# 4_-_POWER.net
KiCad netlist of a schematic drawn in Altium Designer
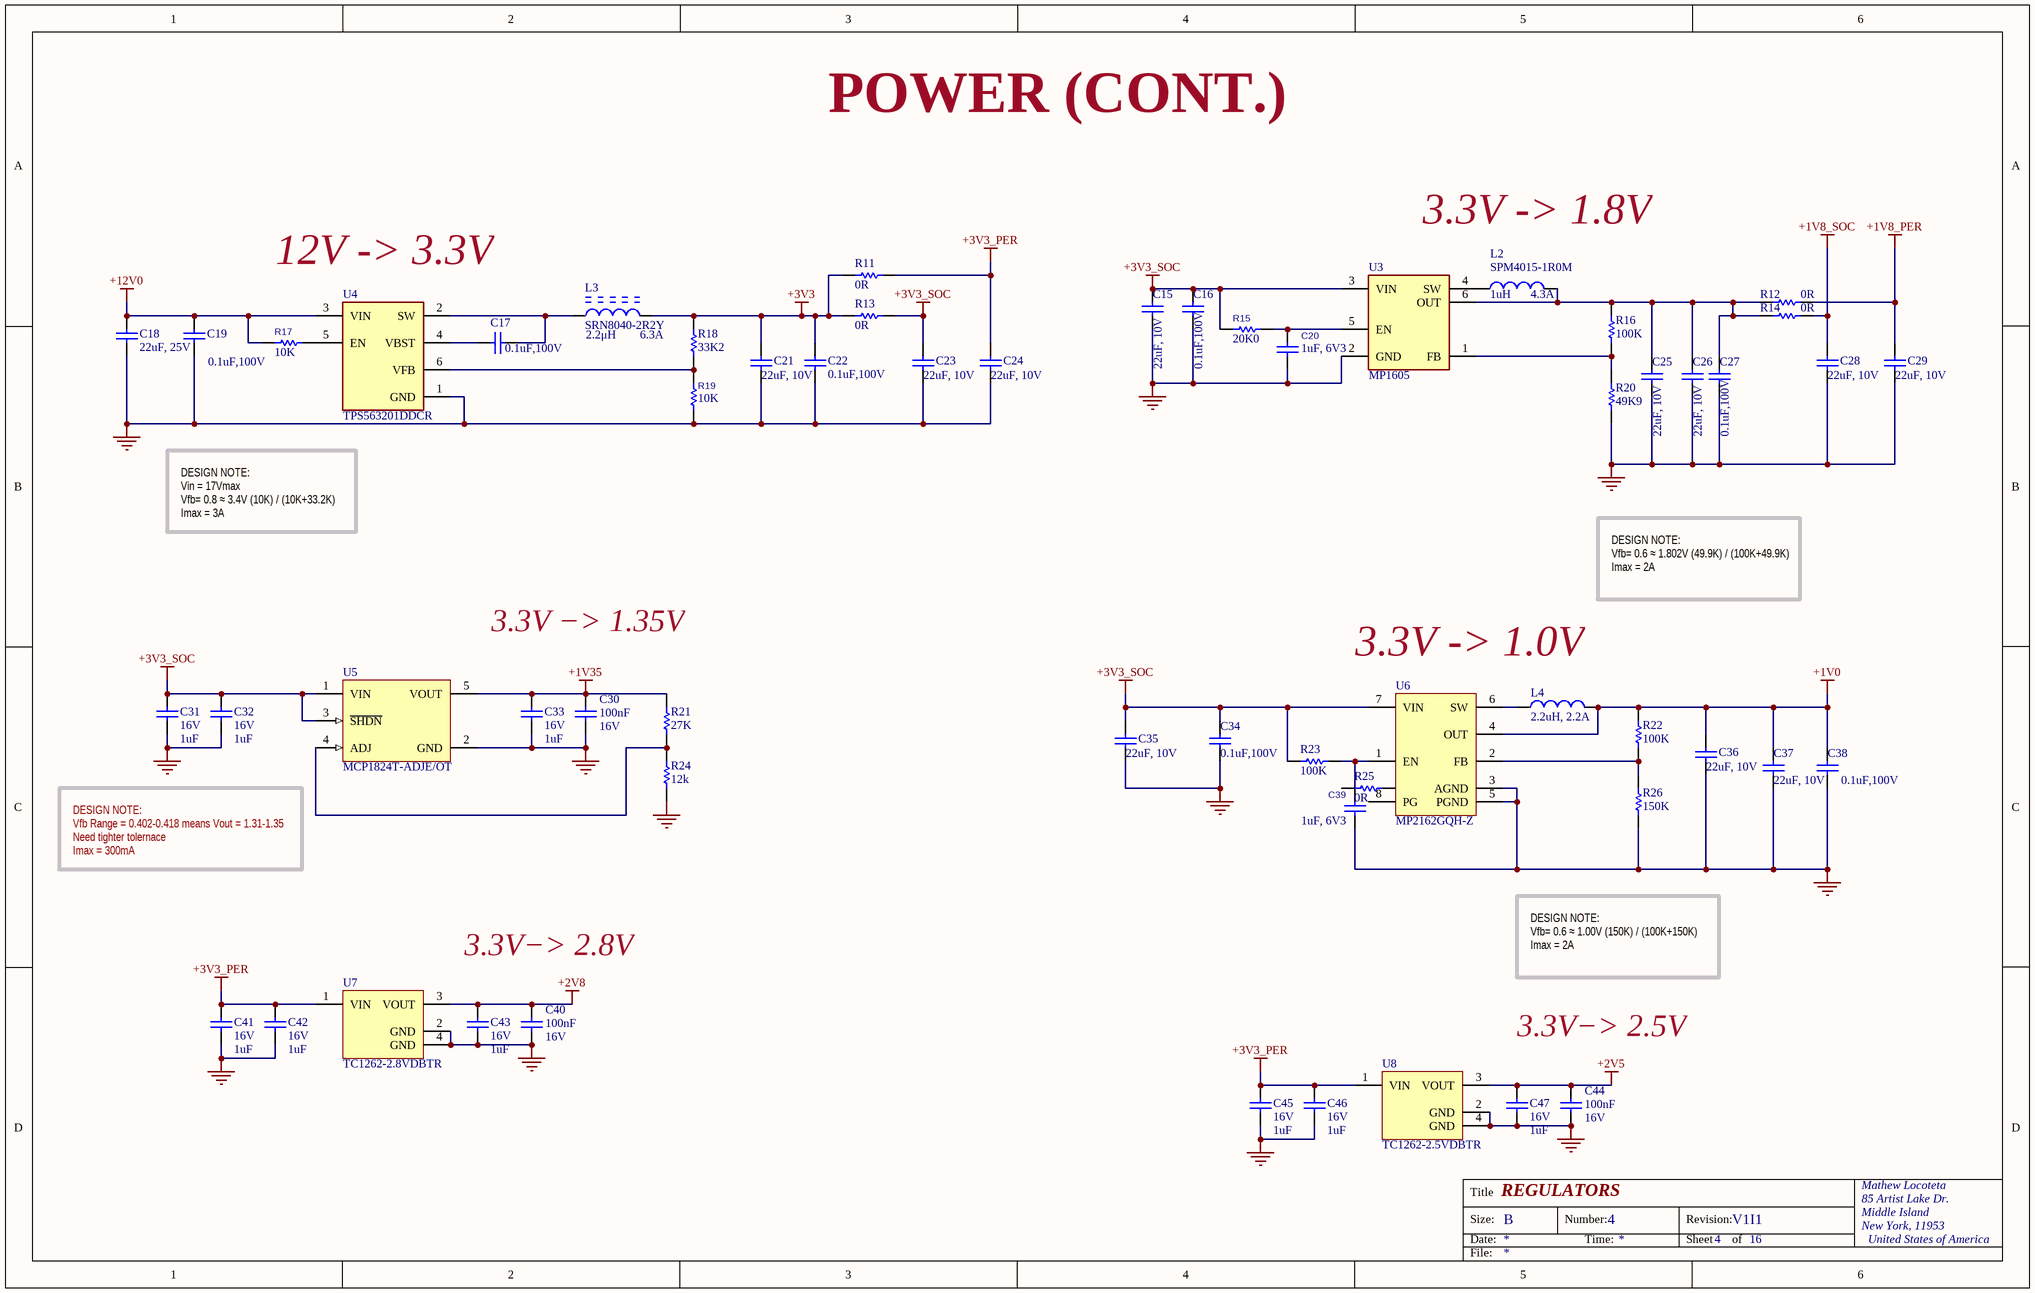
[diagram p0: [4] - POWER (CONT).SchDoc]

(export (version "E")
  (design (tool "Eeschema 10.0.6"))
  (components
    (comp (ref "C15")
      (value "22uF, 10V")
      (footprint "C0805")
      (description "MURATA - GRM21BR61A226ME51L - CAP, MLCC, X5R, 22UF, 10V, 0805")
      (fields
        (field (name "MANUFACTURER") "Murata")
        (field (name "MANUFACTURER PART NUMBER") "GRM21BR61A226ME51L")
      )
      (libsource (lib "DVXC4+ ECU (2)") (part "GRM21BR61A226ME51L"))
    )
    (comp (ref "C16")
      (value "0.1uF,100V")
      (footprint "C0805")
      (description "CAP CER 0.1UF 100V X7R 0805")
      (fields
        (field (name "MANUFACTURER") "Samsung")
        (field (name "MANUFACTURER PART NUMBER") "CL21B104KCFWPNE")
      )
      (libsource (lib "DVXC5 ECU") (part "CL21B104KCFWPNE"))
    )
    (comp (ref "C17")
      (value "0.1uF,100V")
      (footprint "C0805")
      (description "CAP CER 0.1UF 100V X7R 0805")
      (fields
        (field (name "MANUFACTURER") "Samsung")
        (field (name "MANUFACTURER PART NUMBER") "CL21B104KCFWPNE")
      )
      (libsource (lib "DVXC5 ECU") (part "CL21B104KCFWPNE"))
    )
    (comp (ref "C18")
      (value "22uF, 25V")
      (footprint "C1210")
      (description "22µF ±20% 25V Ceramic Capacitor X7R 1210 (3225 Metric)")
      (fields
        (field (name "MANUFACTURER") "Taiyo Yuden")
        (field (name "MANUFACTURER PART NUMBER") "TMK325B7226MMHP")
      )
      (libsource (lib "DVXC4+ ECU (2)") (part "TMK325B7226MMHP"))
    )
    (comp (ref "C19")
      (value "0.1uF,100V")
      (footprint "C0805")
      (description "CAP CER 0.1UF 100V X7R 0805")
      (fields
        (field (name "MANUFACTURER") "Samsung")
        (field (name "MANUFACTURER PART NUMBER") "CL21B104KCFWPNE")
      )
      (libsource (lib "DVXC5 ECU") (part "CL21B104KCFWPNE"))
    )
    (comp (ref "C20")
      (value "1uF, 6V3")
      (footprint "C0402")
      (description "MURATA - GRT155R70J105KE01D - CAP, 1µF, 6.3V, 10%, X7R, 0402")
      (fields
        (field (name "MANUFACTURER") "Murata")
        (field (name "MANUFACTURER PART NUMBER") "GRT155R70J105KE01D")
      )
      (libsource (lib "DVXC4+ ECU (2)") (part "GRT155R70J105KE01D"))
    )
    (comp (ref "C21")
      (value "22uF, 10V")
      (footprint "C0805")
      (description "MURATA - GRM21BR61A226ME51L - CAP, MLCC, X5R, 22UF, 10V, 0805")
      (fields
        (field (name "MANUFACTURER") "Murata")
        (field (name "MANUFACTURER PART NUMBER") "GRM21BR61A226ME51L")
      )
      (libsource (lib "DVXC4+ ECU (2)") (part "GRM21BR61A226ME51L"))
    )
    (comp (ref "C22")
      (value "0.1uF,100V")
      (footprint "C0805")
      (description "CAP CER 0.1UF 100V X7R 0805")
      (fields
        (field (name "MANUFACTURER") "Samsung")
        (field (name "MANUFACTURER PART NUMBER") "CL21B104KCFWPNE")
      )
      (libsource (lib "DVXC5 ECU") (part "CL21B104KCFWPNE"))
    )
    (comp (ref "C23")
      (value "22uF, 10V")
      (footprint "C0805")
      (description "MURATA - GRM21BR61A226ME51L - CAP, MLCC, X5R, 22UF, 10V, 0805")
      (fields
        (field (name "MANUFACTURER") "Murata")
        (field (name "MANUFACTURER PART NUMBER") "GRM21BR61A226ME51L")
      )
      (libsource (lib "DVXC4+ ECU (2)") (part "GRM21BR61A226ME51L"))
    )
    (comp (ref "C24")
      (value "22uF, 10V")
      (footprint "C0805")
      (description "MURATA - GRM21BR61A226ME51L - CAP, MLCC, X5R, 22UF, 10V, 0805")
      (fields
        (field (name "MANUFACTURER") "Murata")
        (field (name "MANUFACTURER PART NUMBER") "GRM21BR61A226ME51L")
      )
      (libsource (lib "DVXC4+ ECU (2)") (part "GRM21BR61A226ME51L"))
    )
    (comp (ref "C25")
      (value "22uF, 10V")
      (footprint "C0805")
      (description "MURATA - GRM21BR61A226ME51L - CAP, MLCC, X5R, 22UF, 10V, 0805")
      (fields
        (field (name "MANUFACTURER") "Murata")
        (field (name "MANUFACTURER PART NUMBER") "GRM21BR61A226ME51L")
      )
      (libsource (lib "DVXC4+ ECU (2)") (part "GRM21BR61A226ME51L"))
    )
    (comp (ref "C26")
      (value "22uF, 10V")
      (footprint "C0805")
      (description "MURATA - GRM21BR61A226ME51L - CAP, MLCC, X5R, 22UF, 10V, 0805")
      (fields
        (field (name "MANUFACTURER") "Murata")
        (field (name "MANUFACTURER PART NUMBER") "GRM21BR61A226ME51L")
      )
      (libsource (lib "DVXC4+ ECU (2)") (part "GRM21BR61A226ME51L"))
    )
    (comp (ref "C27")
      (value "0.1uF,100V")
      (footprint "C0805")
      (description "CAP CER 0.1UF 100V X7R 0805")
      (fields
        (field (name "MANUFACTURER") "Samsung")
        (field (name "MANUFACTURER PART NUMBER") "CL21B104KCFWPNE")
      )
      (libsource (lib "DVXC5 ECU") (part "CL21B104KCFWPNE"))
    )
    (comp (ref "C28")
      (value "22uF, 10V")
      (footprint "C0805")
      (description "MURATA - GRM21BR61A226ME51L - CAP, MLCC, X5R, 22UF, 10V, 0805")
      (fields
        (field (name "MANUFACTURER") "Murata")
        (field (name "MANUFACTURER PART NUMBER") "GRM21BR61A226ME51L")
      )
      (libsource (lib "DVXC4+ ECU (2)") (part "GRM21BR61A226ME51L"))
    )
    (comp (ref "C29")
      (value "22uF, 10V")
      (footprint "C0805")
      (description "MURATA - GRM21BR61A226ME51L - CAP, MLCC, X5R, 22UF, 10V, 0805")
      (fields
        (field (name "MANUFACTURER") "Murata")
        (field (name "MANUFACTURER PART NUMBER") "GRM21BR61A226ME51L")
      )
      (libsource (lib "DVXC4+ ECU (2)") (part "GRM21BR61A226ME51L"))
    )
    (comp (ref "C30")
      (value "0.1uF,16V")
      (footprint "C0402")
      (description "CAP CER 0.1UF 16V X7R 0402")
      (fields
        (field (name "MANUFACTURER") "Samsung")
        (field (name "MANUFACTURER PART NUMBER") "CL05B104KO5VPNC")
        (field (name "CAPACITANCE") "100nF")
        (field (name "VOLTAGE RATING") "16V")
      )
      (libsource (lib "DVXC4+ ECU (2)") (part "CL05B104KO5VPNC"))
    )
    (comp (ref "C31")
      (value "1uF")
      (footprint "C0603")
      (description "Multilayer Ceramic Capacitors MLCC - SMD/SMT 1uF 16V X7R +/-10% 0603 AEC-Q200")
      (fields
        (field (name "MANUFACTURER") "Taiyo Yuden")
        (field (name "MANUFACTURER PART NUMBER") "EMK107B7105KAHT")
        (field (name "VOLTAGE RATING") "16V")
        (field (name "CAPACITANCE") "1uF")
      )
      (libsource (lib "DVXC4+ ECU (2)") (part "EMK107B7105KAHT"))
    )
    (comp (ref "C32")
      (value "1uF")
      (footprint "C0603")
      (description "Multilayer Ceramic Capacitors MLCC - SMD/SMT 1uF 16V X7R +/-10% 0603 AEC-Q200")
      (fields
        (field (name "MANUFACTURER") "Taiyo Yuden")
        (field (name "MANUFACTURER PART NUMBER") "EMK107B7105KAHT")
        (field (name "VOLTAGE RATING") "16V")
        (field (name "CAPACITANCE") "1uF")
      )
      (libsource (lib "DVXC4+ ECU (2)") (part "EMK107B7105KAHT"))
    )
    (comp (ref "C33")
      (value "1uF")
      (footprint "C0603")
      (description "Multilayer Ceramic Capacitors MLCC - SMD/SMT 1uF 16V X7R +/-10% 0603 AEC-Q200")
      (fields
        (field (name "MANUFACTURER") "Taiyo Yuden")
        (field (name "MANUFACTURER PART NUMBER") "EMK107B7105KAHT")
        (field (name "VOLTAGE RATING") "16V")
        (field (name "CAPACITANCE") "1uF")
      )
      (libsource (lib "DVXC4+ ECU (2)") (part "EMK107B7105KAHT"))
    )
    (comp (ref "C34")
      (value "0.1uF,100V")
      (footprint "C0805")
      (description "CAP CER 0.1UF 100V X7R 0805")
      (fields
        (field (name "MANUFACTURER") "Samsung")
        (field (name "MANUFACTURER PART NUMBER") "CL21B104KCFWPNE")
      )
      (libsource (lib "DVXC5 ECU") (part "CL21B104KCFWPNE"))
    )
    (comp (ref "C35")
      (value "22uF, 10V")
      (footprint "C0805")
      (description "MURATA - GRM21BR61A226ME51L - CAP, MLCC, X5R, 22UF, 10V, 0805")
      (fields
        (field (name "MANUFACTURER") "Murata")
        (field (name "MANUFACTURER PART NUMBER") "GRM21BR61A226ME51L")
      )
      (libsource (lib "DVXC4+ ECU (2)") (part "GRM21BR61A226ME51L"))
    )
    (comp (ref "C36")
      (value "22uF, 10V")
      (footprint "C0805")
      (description "MURATA - GRM21BR61A226ME51L - CAP, MLCC, X5R, 22UF, 10V, 0805")
      (fields
        (field (name "MANUFACTURER") "Murata")
        (field (name "MANUFACTURER PART NUMBER") "GRM21BR61A226ME51L")
      )
      (libsource (lib "DVXC4+ ECU (2)") (part "GRM21BR61A226ME51L"))
    )
    (comp (ref "C37")
      (value "22uF, 10V")
      (footprint "C0805")
      (description "MURATA - GRM21BR61A226ME51L - CAP, MLCC, X5R, 22UF, 10V, 0805")
      (fields
        (field (name "MANUFACTURER") "Murata")
        (field (name "MANUFACTURER PART NUMBER") "GRM21BR61A226ME51L")
      )
      (libsource (lib "DVXC4+ ECU (2)") (part "GRM21BR61A226ME51L"))
    )
    (comp (ref "C38")
      (value "0.1uF,100V")
      (footprint "C0805")
      (description "CAP CER 0.1UF 100V X7R 0805")
      (fields
        (field (name "MANUFACTURER") "Samsung")
        (field (name "MANUFACTURER PART NUMBER") "CL21B104KCFWPNE")
      )
      (libsource (lib "DVXC5 ECU") (part "CL21B104KCFWPNE"))
    )
    (comp (ref "C39")
      (value "1uF, 6V3")
      (footprint "C0402")
      (description "MURATA - GRT155R70J105KE01D - CAP, 1µF, 6.3V, 10%, X7R, 0402")
      (fields
        (field (name "MANUFACTURER") "Murata")
        (field (name "MANUFACTURER PART NUMBER") "GRT155R70J105KE01D")
      )
      (libsource (lib "DVXC5 ECU") (part "GRT155R70J105KE01D"))
    )
    (comp (ref "C40")
      (value "0.1uF,16V")
      (footprint "C0402")
      (description "CAP CER 0.1UF 16V X7R 0402")
      (fields
        (field (name "MANUFACTURER") "Samsung")
        (field (name "MANUFACTURER PART NUMBER") "CL05B104KO5VPNC")
        (field (name "CAPACITANCE") "100nF")
        (field (name "VOLTAGE RATING") "16V")
      )
      (libsource (lib "DVXC4+ ECU (2)") (part "CL05B104KO5VPNC"))
    )
    (comp (ref "C41")
      (value "1uF")
      (footprint "C0603")
      (description "Multilayer Ceramic Capacitors MLCC - SMD/SMT 1uF 16V X7R +/-10% 0603 AEC-Q200")
      (fields
        (field (name "MANUFACTURER") "Taiyo Yuden")
        (field (name "MANUFACTURER PART NUMBER") "EMK107B7105KAHT")
        (field (name "VOLTAGE RATING") "16V")
        (field (name "CAPACITANCE") "1uF")
      )
      (libsource (lib "DVXC4+ ECU (2)") (part "EMK107B7105KAHT"))
    )
    (comp (ref "C42")
      (value "1uF")
      (footprint "C0603")
      (description "Multilayer Ceramic Capacitors MLCC - SMD/SMT 1uF 16V X7R +/-10% 0603 AEC-Q200")
      (fields
        (field (name "MANUFACTURER") "Taiyo Yuden")
        (field (name "MANUFACTURER PART NUMBER") "EMK107B7105KAHT")
        (field (name "VOLTAGE RATING") "16V")
        (field (name "CAPACITANCE") "1uF")
      )
      (libsource (lib "DVXC4+ ECU (2)") (part "EMK107B7105KAHT"))
    )
    (comp (ref "C43")
      (value "1uF")
      (footprint "C0603")
      (description "Multilayer Ceramic Capacitors MLCC - SMD/SMT 1uF 16V X7R +/-10% 0603 AEC-Q200")
      (fields
        (field (name "MANUFACTURER") "Taiyo Yuden")
        (field (name "MANUFACTURER PART NUMBER") "EMK107B7105KAHT")
        (field (name "VOLTAGE RATING") "16V")
        (field (name "CAPACITANCE") "1uF")
      )
      (libsource (lib "DVXC4+ ECU (2)") (part "EMK107B7105KAHT"))
    )
    (comp (ref "C44")
      (value "0.1uF,16V")
      (footprint "C0402")
      (description "CAP CER 0.1UF 16V X7R 0402")
      (fields
        (field (name "MANUFACTURER") "Samsung")
        (field (name "MANUFACTURER PART NUMBER") "CL05B104KO5VPNC")
        (field (name "CAPACITANCE") "100nF")
        (field (name "VOLTAGE RATING") "16V")
      )
      (libsource (lib "DVXC4+ ECU (2)") (part "CL05B104KO5VPNC"))
    )
    (comp (ref "C45")
      (value "1uF")
      (footprint "C0603")
      (description "Multilayer Ceramic Capacitors MLCC - SMD/SMT 1uF 16V X7R +/-10% 0603 AEC-Q200")
      (fields
        (field (name "MANUFACTURER") "Taiyo Yuden")
        (field (name "MANUFACTURER PART NUMBER") "EMK107B7105KAHT")
        (field (name "VOLTAGE RATING") "16V")
        (field (name "CAPACITANCE") "1uF")
      )
      (libsource (lib "DVXC4+ ECU (2)") (part "EMK107B7105KAHT"))
    )
    (comp (ref "C46")
      (value "1uF")
      (footprint "C0603")
      (description "Multilayer Ceramic Capacitors MLCC - SMD/SMT 1uF 16V X7R +/-10% 0603 AEC-Q200")
      (fields
        (field (name "MANUFACTURER") "Taiyo Yuden")
        (field (name "MANUFACTURER PART NUMBER") "EMK107B7105KAHT")
        (field (name "VOLTAGE RATING") "16V")
        (field (name "CAPACITANCE") "1uF")
      )
      (libsource (lib "DVXC4+ ECU (2)") (part "EMK107B7105KAHT"))
    )
    (comp (ref "C47")
      (value "1uF")
      (footprint "C0603")
      (description "Multilayer Ceramic Capacitors MLCC - SMD/SMT 1uF 16V X7R +/-10% 0603 AEC-Q200")
      (fields
        (field (name "MANUFACTURER") "Taiyo Yuden")
        (field (name "MANUFACTURER PART NUMBER") "EMK107B7105KAHT")
        (field (name "VOLTAGE RATING") "16V")
        (field (name "CAPACITANCE") "1uF")
      )
      (libsource (lib "DVXC4+ ECU (2)") (part "EMK107B7105KAHT"))
    )
    (comp (ref "L2")
      (value "SPM4015-1R0M")
      (description "Fixed Inductors 1.0uH 39mOhms 6.7A 4.4x4.1x1.5mm")
      (fields
        (field (name "MANUFACTURER") "TDK")
        (field (name "TOLERANCE") "20%")
        (field (name "INDUCTANCE") "1uH")
        (field (name "CURRENT RATING") "4.3A")
      )
      (libsource (lib "DVXC4+ ECU (2)") (part "SPM4015-1R0M"))
    )
    (comp (ref "L3")
      (value "SRN8040-2R2Y")
      (footprint "BOUR-SRN8040_V")
      (fields
        (field (name "MANUFACTURER") "Bourns")
        (field (name "TOLERANCE") "±30%")
        (field (name "CURRENT, RATING") "6.3A")
        (field (name "INDUCTANCE") "2.2μH")
      )
      (libsource (lib "Altium Content Vault") (part "IND-FERR-2"))
    )
    (comp (ref "L4")
      (value "2.2uH, 2.2A")
      (description "FIXED IND 2.2UH 2.2A 108 MOHM")
      (fields
        (field (name "MANUFACTURER") "Murata")
        (field (name "MANUFACTURER PART NUMBER") "1239AS-H-2R2M=P2")
      )
      (libsource (lib "DVXC4+ ECU (2)") (part "1239AS-H-2R2M=P2"))
    )
    (comp (ref "R11")
      (value "0R")
      (footprint "r0805")
      (fields
        (field (name "MANUFACTURER") "Stackpole Electronics")
        (field (name "MANUFACTURER PART NUMBER") "RMCF0805ZT0R00")
      )
      (libsource (lib "DVXC4+ ECU (2)") (part "RMCF0805ZT0R00"))
    )
    (comp (ref "R12")
      (value "0R")
      (footprint "r0805")
      (fields
        (field (name "MANUFACTURER") "Stackpole Electronics")
        (field (name "MANUFACTURER PART NUMBER") "RMCF0805ZT0R00")
      )
      (libsource (lib "DVXC4+ ECU (2)") (part "RMCF0805ZT0R00"))
    )
    (comp (ref "R13")
      (value "0R")
      (footprint "r0805")
      (fields
        (field (name "MANUFACTURER") "Stackpole Electronics")
        (field (name "MANUFACTURER PART NUMBER") "RMCF0805ZT0R00")
      )
      (libsource (lib "DVXC4+ ECU (2)") (part "RMCF0805ZT0R00"))
    )
    (comp (ref "R14")
      (value "0R")
      (footprint "r0805")
      (fields
        (field (name "MANUFACTURER") "Stackpole Electronics")
        (field (name "MANUFACTURER PART NUMBER") "RMCF0805ZT0R00")
      )
      (libsource (lib "DVXC4+ ECU (2)") (part "RMCF0805ZT0R00"))
    )
    (comp (ref "R15")
      (value "20K0")
      (footprint "R0402")
      (description "RES 20K OHM 1% 1/16W 0402")
      (fields (field (name "TOLERANCE") "1%"))
      (libsource (lib "DVXC4+ ECU (2)") (part "RMCF0402FT20K0"))
    )
    (comp (ref "R16")
      (value "100K")
      (footprint "R0402")
      (description "RES 100K OHM 1% 1/16W 0402")
      (fields
        (field (name "MANUFACTURER") "Stackpole Electronics")
        (field (name "MANUFACTURER PART NUMBER") "RMCF0402FT100K")
      )
      (libsource (lib "DVXC4+ ECU (2)") (part "RMCF0402FT100K"))
    )
    (comp (ref "R17")
      (value "10K")
      (footprint "R0402")
      (description "RES 10K OHM 1% 1/16W 0402")
      (fields
        (field (name "MANUFACTURER") "Stackpole Electronics")
        (field (name "MANUFACTURER PART NUMBER") "RMCF0402FT10K0")
      )
      (libsource (lib "DVXC4+ ECU (2)") (part "RMCF0402FT10K0"))
    )
    (comp (ref "R18")
      (value "33K2")
      (footprint "R0402")
      (description "RES 33.2K OHM 1% 1/16W 0402")
      (fields
        (field (name "MANUFACTURER") "Stackpole Electronics")
        (field (name "MANUFACTURER PART NUMBER") "RMCF0402FT33K2")
      )
      (libsource (lib "DVXC4+ ECU (2)") (part "RMCF0402FT33K2"))
    )
    (comp (ref "R19")
      (value "10K")
      (footprint "R0402")
      (description "RES 10K OHM 1% 1/16W 0402")
      (fields
        (field (name "MANUFACTURER") "Stackpole Electronics")
        (field (name "MANUFACTURER PART NUMBER") "RMCF0402FT10K0")
      )
      (libsource (lib "DVXC4+ ECU (2)") (part "RMCF0402FT10K0"))
    )
    (comp (ref "R20")
      (value "49K9")
      (footprint "R0402")
      (fields
        (field (name "MANUFACTURER") "Stackpole Electronics")
        (field (name "MANUFACTURER PART NUMBER") "RMCF0402FT49K9")
        (field (name "TOLERANCE") "1%")
      )
      (libsource (lib "DVXC4+ ECU (2)") (part "RMCF0402FT49K9"))
    )
    (comp (ref "R21")
      (value "27K")
      (footprint "RESC1005X40X25ML05T05")
      (fields (field (name "PART NUMBER") "CRCW040227K0FKED") (field (name "MANUFACTURER") "Vishay Dale"))
      (libsource (lib "Altium Content Vault") (part "RES"))
    )
    (comp (ref "R22")
      (value "ERJ-2RKF1003X")
      (footprint "RESC1005X40X25LL05T05")
      (description "Chip Resistor, 100 KOhm, +/- 1%, 100 mW, -55 to 155 degC, 0402 (1005 Metric), RoHS, Tape and Reel")
      (fields
        (field (name "TOLERANCE") "1%")
        (field (name "RESISTANCE") "100K")
        (field (name "MANUFACTURER") "Basic Passives")
      )
      (libsource (lib "Altium Content Vault") (part "RES-2"))
    )
    (comp (ref "R23")
      (value "100K")
      (footprint "R0402")
      (description "RES 100K OHM 1% 1/16W 0402")
      (fields
        (field (name "MANUFACTURER") "Stackpole Electronics")
        (field (name "MANUFACTURER PART NUMBER") "RMCF0402FT100K")
      )
      (libsource (lib "DVXC4+ ECU (2)") (part "RMCF0402FT100K"))
    )
    (comp (ref "R24")
      (value "12k")
      (footprint "RESC1005X40X25NL05T05")
      (fields (field (name "PART NUMBER") "CRCW040212K0FKED") (field (name "MANUFACTURER") "Vishay Dale"))
      (libsource (lib "Altium Content Vault") (part "RES"))
    )
    (comp (ref "R25")
      (value "0R")
      (footprint "r0805")
      (fields
        (field (name "MANUFACTURER") "Stackpole Electronics")
        (field (name "MANUFACTURER PART NUMBER") "RMCF0805ZT0R00")
      )
      (libsource (lib "DVXC4+ ECU (2)") (part "RMCF0805ZT0R00"))
    )
    (comp (ref "R26")
      (value "150K")
      (footprint "R0402")
      (description "RES 150K OHM 1% 1/16W 0402")
      (fields
        (field (name "MANUFACTURER") "Stackpole Electronics")
        (field (name "MANUFACTURER PART NUMBER") "RMCF0402FT150K")
      )
      (libsource (lib "DVXC4+ ECU (2)") (part "RMCF0402FT150K"))
    )
    (comp (ref "U3")
      (value "MP1605")
      (description "Monolithic Step down,, 2 A , 2.3-5.5V 0.6Vmin out")
      (libsource (lib "DVXC4+ ECU (2)") (part "MP1605"))
    )
    (comp (ref "U4")
      (value "TPS563201DDCR")
      (description "IC REG BUCK ADJ 3A TSOT23-6")
      (fields (field (name "MANUFACTURER") "Texas Instruments"))
      (libsource (lib "DVXC4+ ECU (2)") (part "TPS563201DDCR"))
    )
    (comp (ref "U5")
      (value "MCP1824T-ADJE/OT")
      (footprint "SOT-23-OT5_M")
      (libsource (lib "Altium Content Vault") (part "PM-LINEREG-MCP1824-IL5C"))
    )
    (comp (ref "U6")
      (value "MP2162GQH-Z")
      (description "Conv DC-DC Single Step Down 2.5V 6V 8-Pin QFN EP T/R")
      (fields (field (name "MANUFACTURER") "Monolithic Power Systems"))
      (libsource (lib "DVXC5 ECU") (part "MP2162GQH-Z"))
    )
    (comp (ref "U7")
      (value "TC1262-2.8VDBTR")
      (footprint "SOT-223-DB3_N")
      (description "500mA Fixed Output CMOS LDO, 3-Pin SOT-223, Extended Temperature, Tape and Reel")
      (libsource (lib "Altium Content Vault") (part "PM-LINEREG-TC1262-IL4"))
    )
    (comp (ref "U8")
      (value "TC1262-2.5VDBTR")
      (footprint "SOT-223-DB3_M")
      (description "500mA Fixed Output CMOS LDO, 3-Pin SOT-223, Extended Temperature, Tape and Reel")
      (libsource (lib "Altium Content Vault") (part "PM-LINEREG-TC1262-IL4"))
    )
  )
  (nets
    (net (code "1") (name "+1V0") (class "Default")
      (node (ref "C36") (pin "2") (pinfunction "2_2") (pintype "passive"))
      (node (ref "C37") (pin "2") (pinfunction "2_2") (pintype "passive"))
      (node (ref "C38") (pin "2") (pinfunction "2_2") (pintype "passive"))
      (node (ref "L4") (pin "2") (pinfunction "2_2") (pintype "passive"))
      (node (ref "R22") (pin "2") (pinfunction "2_2") (pintype "passive"))
      (node (ref "U6") (pin "4") (pinfunction "OUT_4") (pintype "passive"))
    )
    (net (code "2") (name "+1V8_PER") (class "Default")
      (node (ref "C29") (pin "2") (pinfunction "2_2") (pintype "passive"))
      (node (ref "R12") (pin "2") (pinfunction "2_2") (pintype "passive"))
    )
    (net (code "3") (name "+1V8_SOC") (class "Default")
      (node (ref "C28") (pin "2") (pinfunction "2_2") (pintype "passive"))
      (node (ref "R14") (pin "2") (pinfunction "2_2") (pintype "passive"))
    )
    (net (code "4") (name "+1V35") (class "Default")
      (node (ref "C30") (pin "1") (pinfunction "1_1") (pintype "passive"))
      (node (ref "C33") (pin "2") (pinfunction "2_2") (pintype "passive"))
      (node (ref "R21") (pin "2") (pinfunction "2_2") (pintype "passive"))
      (node (ref "U5") (pin "5") (pinfunction "VOUT_5") (pintype "power_in"))
    )
    (net (code "5") (name "+2V5") (class "Default")
      (node (ref "C44") (pin "1") (pinfunction "1_1") (pintype "passive"))
      (node (ref "C47") (pin "2") (pinfunction "2_2") (pintype "passive"))
      (node (ref "U8") (pin "3") (pinfunction "VOUT_3") (pintype "power_in"))
    )
    (net (code "6") (name "+2V8") (class "Default")
      (node (ref "C40") (pin "1") (pinfunction "1_1") (pintype "passive"))
      (node (ref "C43") (pin "2") (pinfunction "2_2") (pintype "passive"))
      (node (ref "U7") (pin "3") (pinfunction "VOUT_3") (pintype "power_in"))
    )
    (net (code "7") (name "+3V3") (class "Default")
      (node (ref "C21") (pin "2") (pinfunction "2_2") (pintype "passive"))
      (node (ref "C22") (pin "1") (pinfunction "1_1") (pintype "passive"))
      (node (ref "L3") (pin "2") (pinfunction "2_2") (pintype "passive"))
      (node (ref "R11") (pin "2") (pinfunction "2_2") (pintype "passive"))
      (node (ref "R13") (pin "2") (pinfunction "2_2") (pintype "passive"))
      (node (ref "R18") (pin "2") (pinfunction "2_2") (pintype "passive"))
    )
    (net (code "8") (name "+3V3_PER") (class "Default")
      (node (ref "C24") (pin "2") (pinfunction "2_2") (pintype "passive"))
      (node (ref "C41") (pin "2") (pinfunction "2_2") (pintype "passive"))
      (node (ref "C42") (pin "2") (pinfunction "2_2") (pintype "passive"))
      (node (ref "C45") (pin "2") (pinfunction "2_2") (pintype "passive"))
      (node (ref "C46") (pin "2") (pinfunction "2_2") (pintype "passive"))
      (node (ref "R11") (pin "1") (pinfunction "1_1") (pintype "passive"))
      (node (ref "U7") (pin "1") (pinfunction "VIN_1") (pintype "power_in"))
      (node (ref "U8") (pin "1") (pinfunction "VIN_1") (pintype "power_in"))
    )
    (net (code "9") (name "+3V3_SOC") (class "Default")
      (node (ref "C15") (pin "2") (pinfunction "2_2") (pintype "passive"))
      (node (ref "C16") (pin "1") (pinfunction "1_1") (pintype "passive"))
      (node (ref "C23") (pin "2") (pinfunction "2_2") (pintype "passive"))
      (node (ref "C31") (pin "2") (pinfunction "2_2") (pintype "passive"))
      (node (ref "C32") (pin "2") (pinfunction "2_2") (pintype "passive"))
      (node (ref "C34") (pin "1") (pinfunction "1_1") (pintype "passive"))
      (node (ref "C35") (pin "2") (pinfunction "2_2") (pintype "passive"))
      (node (ref "R13") (pin "1") (pinfunction "1_1") (pintype "passive"))
      (node (ref "R15") (pin "2") (pinfunction "2_2") (pintype "passive"))
      (node (ref "R23") (pin "1") (pinfunction "1_1") (pintype "passive"))
      (node (ref "U3") (pin "3") (pinfunction "VIN_3") (pintype "passive"))
      (node (ref "U5") (pin "1") (pinfunction "VIN_1") (pintype "power_in"))
      (node (ref "U5") (pin "3") (pinfunction "~{SHDN}_3") (pintype "input"))
      (node (ref "U6") (pin "7") (pinfunction "VIN_7") (pintype "passive"))
    )
    (net (code "10") (name "+12V0") (class "Default")
      (node (ref "C18") (pin "2") (pinfunction "2_2") (pintype "passive"))
      (node (ref "C19") (pin "2") (pinfunction "2_2") (pintype "passive"))
      (node (ref "R17") (pin "1") (pinfunction "1_1") (pintype "passive"))
      (node (ref "U4") (pin "3") (pinfunction "VIN_3") (pintype "passive"))
    )
    (net (code "11") (name "GND") (class "Default")
      (node (ref "C15") (pin "1") (pinfunction "1_1") (pintype "passive"))
      (node (ref "C16") (pin "2") (pinfunction "2_2") (pintype "passive"))
      (node (ref "C18") (pin "1") (pinfunction "1_1") (pintype "passive"))
      (node (ref "C19") (pin "1") (pinfunction "1_1") (pintype "passive"))
      (node (ref "C20") (pin "1") (pinfunction "1_1") (pintype "passive"))
      (node (ref "C21") (pin "1") (pinfunction "1_1") (pintype "passive"))
      (node (ref "C22") (pin "2") (pinfunction "2_2") (pintype "passive"))
      (node (ref "C23") (pin "1") (pinfunction "1_1") (pintype "passive"))
      (node (ref "C24") (pin "1") (pinfunction "1_1") (pintype "passive"))
      (node (ref "C25") (pin "1") (pinfunction "1_1") (pintype "passive"))
      (node (ref "C26") (pin "1") (pinfunction "1_1") (pintype "passive"))
      (node (ref "C27") (pin "2") (pinfunction "2_2") (pintype "passive"))
      (node (ref "C28") (pin "1") (pinfunction "1_1") (pintype "passive"))
      (node (ref "C29") (pin "1") (pinfunction "1_1") (pintype "passive"))
      (node (ref "C30") (pin "2") (pinfunction "2_2") (pintype "passive"))
      (node (ref "C31") (pin "1") (pinfunction "1_1") (pintype "passive"))
      (node (ref "C32") (pin "1") (pinfunction "1_1") (pintype "passive"))
      (node (ref "C33") (pin "1") (pinfunction "1_1") (pintype "passive"))
      (node (ref "C34") (pin "2") (pinfunction "2_2") (pintype "passive"))
      (node (ref "C35") (pin "1") (pinfunction "1_1") (pintype "passive"))
      (node (ref "C36") (pin "1") (pinfunction "1_1") (pintype "passive"))
      (node (ref "C37") (pin "1") (pinfunction "1_1") (pintype "passive"))
      (node (ref "C38") (pin "1") (pinfunction "1_1") (pintype "passive"))
      (node (ref "C39") (pin "1") (pinfunction "1_1") (pintype "passive"))
      (node (ref "C40") (pin "2") (pinfunction "2_2") (pintype "passive"))
      (node (ref "C41") (pin "1") (pinfunction "1_1") (pintype "passive"))
      (node (ref "C42") (pin "1") (pinfunction "1_1") (pintype "passive"))
      (node (ref "C43") (pin "1") (pinfunction "1_1") (pintype "passive"))
      (node (ref "C44") (pin "2") (pinfunction "2_2") (pintype "passive"))
      (node (ref "C45") (pin "1") (pinfunction "1_1") (pintype "passive"))
      (node (ref "C46") (pin "1") (pinfunction "1_1") (pintype "passive"))
      (node (ref "C47") (pin "1") (pinfunction "1_1") (pintype "passive"))
      (node (ref "R19") (pin "1") (pinfunction "1_1") (pintype "passive"))
      (node (ref "R20") (pin "1") (pinfunction "1_1") (pintype "passive"))
      (node (ref "R24") (pin "1") (pinfunction "1_1") (pintype "passive"))
      (node (ref "R26") (pin "1") (pinfunction "1_1") (pintype "passive"))
      (node (ref "U3") (pin "2") (pinfunction "GND_2") (pintype "passive"))
      (node (ref "U4") (pin "1") (pinfunction "GND_1") (pintype "passive"))
      (node (ref "U5") (pin "2") (pinfunction "GND_2") (pintype "power_in"))
      (node (ref "U6") (pin "3") (pinfunction "AGND_3") (pintype "passive"))
      (node (ref "U6") (pin "5") (pinfunction "PGND_5") (pintype "passive"))
      (node (ref "U7") (pin "2") (pinfunction "GND_2") (pintype "power_in"))
      (node (ref "U7") (pin "4") (pinfunction "GND_4") (pintype "power_in"))
      (node (ref "U8") (pin "2") (pinfunction "GND_2") (pintype "power_in"))
      (node (ref "U8") (pin "4") (pinfunction "GND_4") (pintype "power_in"))
    )
    (net (code "12") (name "Net-(U3-EN)") (class "Default")
      (node (ref "C20") (pin "2") (pinfunction "2_2") (pintype "passive"))
      (node (ref "R15") (pin "1") (pinfunction "1_1") (pintype "passive"))
      (node (ref "U3") (pin "5") (pinfunction "EN_5") (pintype "passive"))
    )
    (net (code "13") (name "Net-(U3-FB)") (class "Default")
      (node (ref "R16") (pin "1") (pinfunction "1_1") (pintype "passive"))
      (node (ref "R20") (pin "2") (pinfunction "2_2") (pintype "passive"))
      (node (ref "U3") (pin "1") (pinfunction "FB_1") (pintype "passive"))
    )
    (net (code "14") (name "Net-(U3-OUT)") (class "Default")
      (node (ref "C25") (pin "2") (pinfunction "2_2") (pintype "passive"))
      (node (ref "C26") (pin "2") (pinfunction "2_2") (pintype "passive"))
      (node (ref "C27") (pin "1") (pinfunction "1_1") (pintype "passive"))
      (node (ref "L2") (pin "2") (pinfunction "2_2") (pintype "passive"))
      (node (ref "R12") (pin "1") (pinfunction "1_1") (pintype "passive"))
      (node (ref "R14") (pin "1") (pinfunction "1_1") (pintype "passive"))
      (node (ref "R16") (pin "2") (pinfunction "2_2") (pintype "passive"))
      (node (ref "U3") (pin "6") (pinfunction "OUT_6") (pintype "passive"))
    )
    (net (code "15") (name "Net-(U3-SW)") (class "Default")
      (node (ref "L2") (pin "1") (pinfunction "1_1") (pintype "passive"))
      (node (ref "U3") (pin "4") (pinfunction "SW_4") (pintype "passive"))
    )
    (net (code "16") (name "Net-(U4-EN)") (class "Default")
      (node (ref "R17") (pin "2") (pinfunction "2_2") (pintype "passive"))
      (node (ref "U4") (pin "5") (pinfunction "EN_5") (pintype "passive"))
    )
    (net (code "17") (name "Net-(U4-SW)") (class "Default")
      (node (ref "C17") (pin "1") (pinfunction "1_1") (pintype "passive"))
      (node (ref "L3") (pin "1") (pinfunction "1_1") (pintype "passive"))
      (node (ref "U4") (pin "2") (pinfunction "SW_2") (pintype "passive"))
    )
    (net (code "18") (name "Net-(U4-VBST)") (class "Default")
      (node (ref "C17") (pin "2") (pinfunction "2_2") (pintype "passive"))
      (node (ref "U4") (pin "4") (pinfunction "VBST_4") (pintype "passive"))
    )
    (net (code "19") (name "Net-(U4-VFB)") (class "Default")
      (node (ref "R18") (pin "1") (pinfunction "1_1") (pintype "passive"))
      (node (ref "R19") (pin "2") (pinfunction "2_2") (pintype "passive"))
      (node (ref "U4") (pin "6") (pinfunction "VFB_6") (pintype "passive"))
    )
    (net (code "20") (name "Net-(U5-ADJ)") (class "Default")
      (node (ref "R21") (pin "1") (pinfunction "1_1") (pintype "passive"))
      (node (ref "R24") (pin "2") (pinfunction "2_2") (pintype "passive"))
      (node (ref "U5") (pin "4") (pinfunction "ADJ_4") (pintype "input"))
    )
    (net (code "21") (name "Net-(U6-EN)") (class "Default")
      (node (ref "C39") (pin "2") (pinfunction "2_2") (pintype "passive"))
      (node (ref "R23") (pin "2") (pinfunction "2_2") (pintype "passive"))
      (node (ref "U6") (pin "1") (pinfunction "EN_1") (pintype "passive"))
    )
    (net (code "22") (name "Net-(U6-FB)") (class "Default")
      (node (ref "R22") (pin "1") (pinfunction "1_1") (pintype "passive"))
      (node (ref "R26") (pin "2") (pinfunction "2_2") (pintype "passive"))
      (node (ref "U6") (pin "2") (pinfunction "FB_2") (pintype "passive"))
    )
    (net (code "23") (name "Net-(U6-SW)") (class "Default")
      (node (ref "L4") (pin "1") (pinfunction "1_1") (pintype "passive"))
      (node (ref "U6") (pin "6") (pinfunction "SW_6") (pintype "passive"))
    )
    (net (code "24") (name "unconnected-(R25-Pad1)") (class "Default")
      (node (ref "R25") (pin "1") (pinfunction "1_1") (pintype "passive"))
    )
    (net (code "25") (name "unconnected-(R25-Pad2)") (class "Default")
      (node (ref "R25") (pin "2") (pinfunction "2_2") (pintype "passive"))
    )
    (net (code "26") (name "unconnected-(U6-PG-Pad8)") (class "Default")
      (node (ref "U6") (pin "8") (pinfunction "PG_8") (pintype "passive"))
    )
  )
)
